# Dual_line_PS.net
KiCad netlist of a schematic drawn in EAGLE
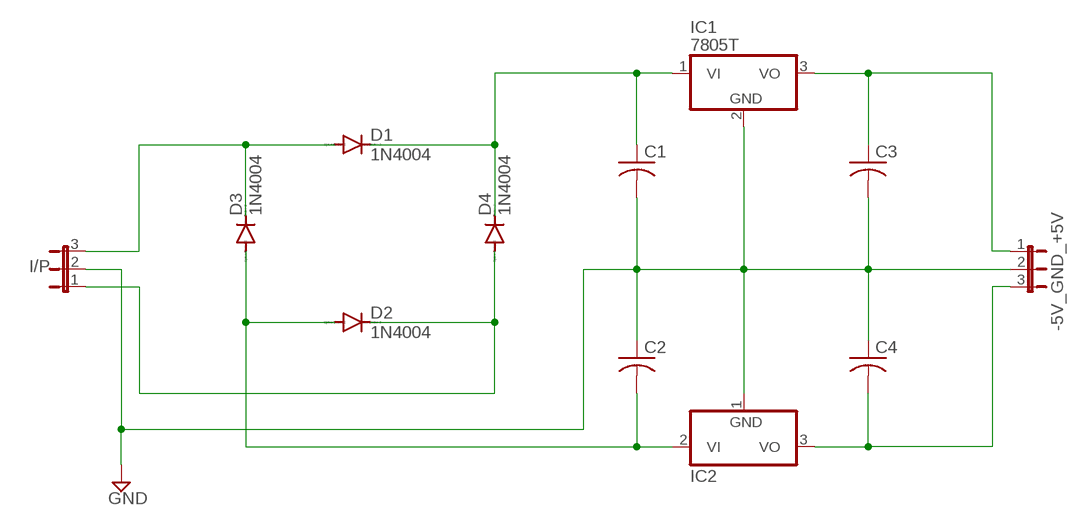
[diagram p0: schematic, sheet 1]

(export (version "E")
  (design (tool "Eeschema 10.0.6"))
  (components
    (comp (ref "-5V_GND_+5V")
      (value "JP2E")
      (footprint "eagle-import:JP2")
      (libsource (lib "eagle-import") (part "JP2E"))
    )
    (comp (ref "C1")
      (value "C-US025-024X044")
      (footprint "eagle-import:C025-024X044")
      (libsource (lib "eagle-import") (part "C-US025-024X044"))
    )
    (comp (ref "C2")
      (value "C-US025-024X044")
      (footprint "eagle-import:C025-024X044")
      (libsource (lib "eagle-import") (part "C-US025-024X044"))
    )
    (comp (ref "C3")
      (value "C-US025-024X044")
      (footprint "eagle-import:C025-024X044")
      (libsource (lib "eagle-import") (part "C-US025-024X044"))
    )
    (comp (ref "C4")
      (value "C-US025-024X044")
      (footprint "eagle-import:C025-024X044")
      (libsource (lib "eagle-import") (part "C-US025-024X044"))
    )
    (comp (ref "D1")
      (value "1N4004")
      (footprint "eagle-import:DO41-10")
      (libsource (lib "eagle-import") (part "1N4004"))
    )
    (comp (ref "D2")
      (value "1N4004")
      (footprint "eagle-import:DO41-10")
      (libsource (lib "eagle-import") (part "1N4004"))
    )
    (comp (ref "D3")
      (value "1N4004")
      (footprint "eagle-import:DO41-10")
      (libsource (lib "eagle-import") (part "1N4004"))
    )
    (comp (ref "D4")
      (value "1N4004")
      (footprint "eagle-import:DO41-10")
      (libsource (lib "eagle-import") (part "1N4004"))
    )
    (comp (ref "I/P")
      (value "JP2E")
      (footprint "eagle-import:JP2")
      (libsource (lib "eagle-import") (part "JP2E"))
    )
    (comp (ref "IC1")
      (value "7805T")
      (footprint "eagle-import:TO220H")
      (libsource (lib "eagle-import") (part "78T05"))
    )
    (comp (ref "IC2")
      (value "7905T")
      (footprint "eagle-import:TO220H")
      (libsource (lib "eagle-import") (part "79T05"))
    )
  )
  (nets
    (net (code "1") (name "GND") (class "Default")
      (node (ref "-5V_GND_+5V") (pin "2") (pinfunction "2_2") (pintype "passive"))
      (node (ref "C1") (pin "2") (pinfunction "2_2") (pintype "passive"))
      (node (ref "C2") (pin "1") (pinfunction "1_1") (pintype "passive"))
      (node (ref "C3") (pin "2") (pinfunction "2_2") (pintype "passive"))
      (node (ref "C4") (pin "1") (pinfunction "1_1") (pintype "passive"))
      (node (ref "I/P") (pin "2") (pinfunction "2_2") (pintype "passive"))
      (node (ref "IC1") (pin "2") (pinfunction "GND_2") (pintype "passive"))
      (node (ref "IC2") (pin "1") (pinfunction "GND_1") (pintype "passive"))
    )
    (net (code "2") (name "Net-(D1-PadA)") (class "Default")
      (node (ref "D1") (pin "A") (pinfunction "A_A") (pintype "passive"))
      (node (ref "D3") (pin "C") (pinfunction "C_C") (pintype "passive"))
      (node (ref "I/P") (pin "3") (pinfunction "3_3") (pintype "passive"))
    )
    (net (code "3") (name "Net-(D2-PadC)") (class "Default")
      (node (ref "D2") (pin "C") (pinfunction "C_C") (pintype "passive"))
      (node (ref "D4") (pin "A") (pinfunction "A_A") (pintype "passive"))
      (node (ref "I/P") (pin "1") (pinfunction "1_1") (pintype "passive"))
    )
    (net (code "4") (name "Net-(IC1-VI)") (class "Default")
      (node (ref "C1") (pin "1") (pinfunction "1_1") (pintype "passive"))
      (node (ref "D1") (pin "C") (pinfunction "C_C") (pintype "passive"))
      (node (ref "D4") (pin "C") (pinfunction "C_C") (pintype "passive"))
      (node (ref "IC1") (pin "1") (pinfunction "VI_1") (pintype "input"))
    )
    (net (code "5") (name "Net-(IC1-VO)") (class "Default")
      (node (ref "-5V_GND_+5V") (pin "1") (pinfunction "1_1") (pintype "passive"))
      (node (ref "C3") (pin "1") (pinfunction "1_1") (pintype "passive"))
      (node (ref "IC1") (pin "3") (pinfunction "VO_3") (pintype "passive"))
    )
    (net (code "6") (name "Net-(IC2-VI)") (class "Default")
      (node (ref "C2") (pin "2") (pinfunction "2_2") (pintype "passive"))
      (node (ref "D2") (pin "A") (pinfunction "A_A") (pintype "passive"))
      (node (ref "D3") (pin "A") (pinfunction "A_A") (pintype "passive"))
      (node (ref "IC2") (pin "2") (pinfunction "VI_2") (pintype "input"))
    )
    (net (code "7") (name "Net-(IC2-VO)") (class "Default")
      (node (ref "-5V_GND_+5V") (pin "3") (pinfunction "3_3") (pintype "passive"))
      (node (ref "C4") (pin "2") (pinfunction "2_2") (pintype "passive"))
      (node (ref "IC2") (pin "3") (pinfunction "VO_3") (pintype "passive"))
    )
  )
)
